# GPS_tracker_MCU.net
KiCad netlist of a schematic drawn in Altium Designer
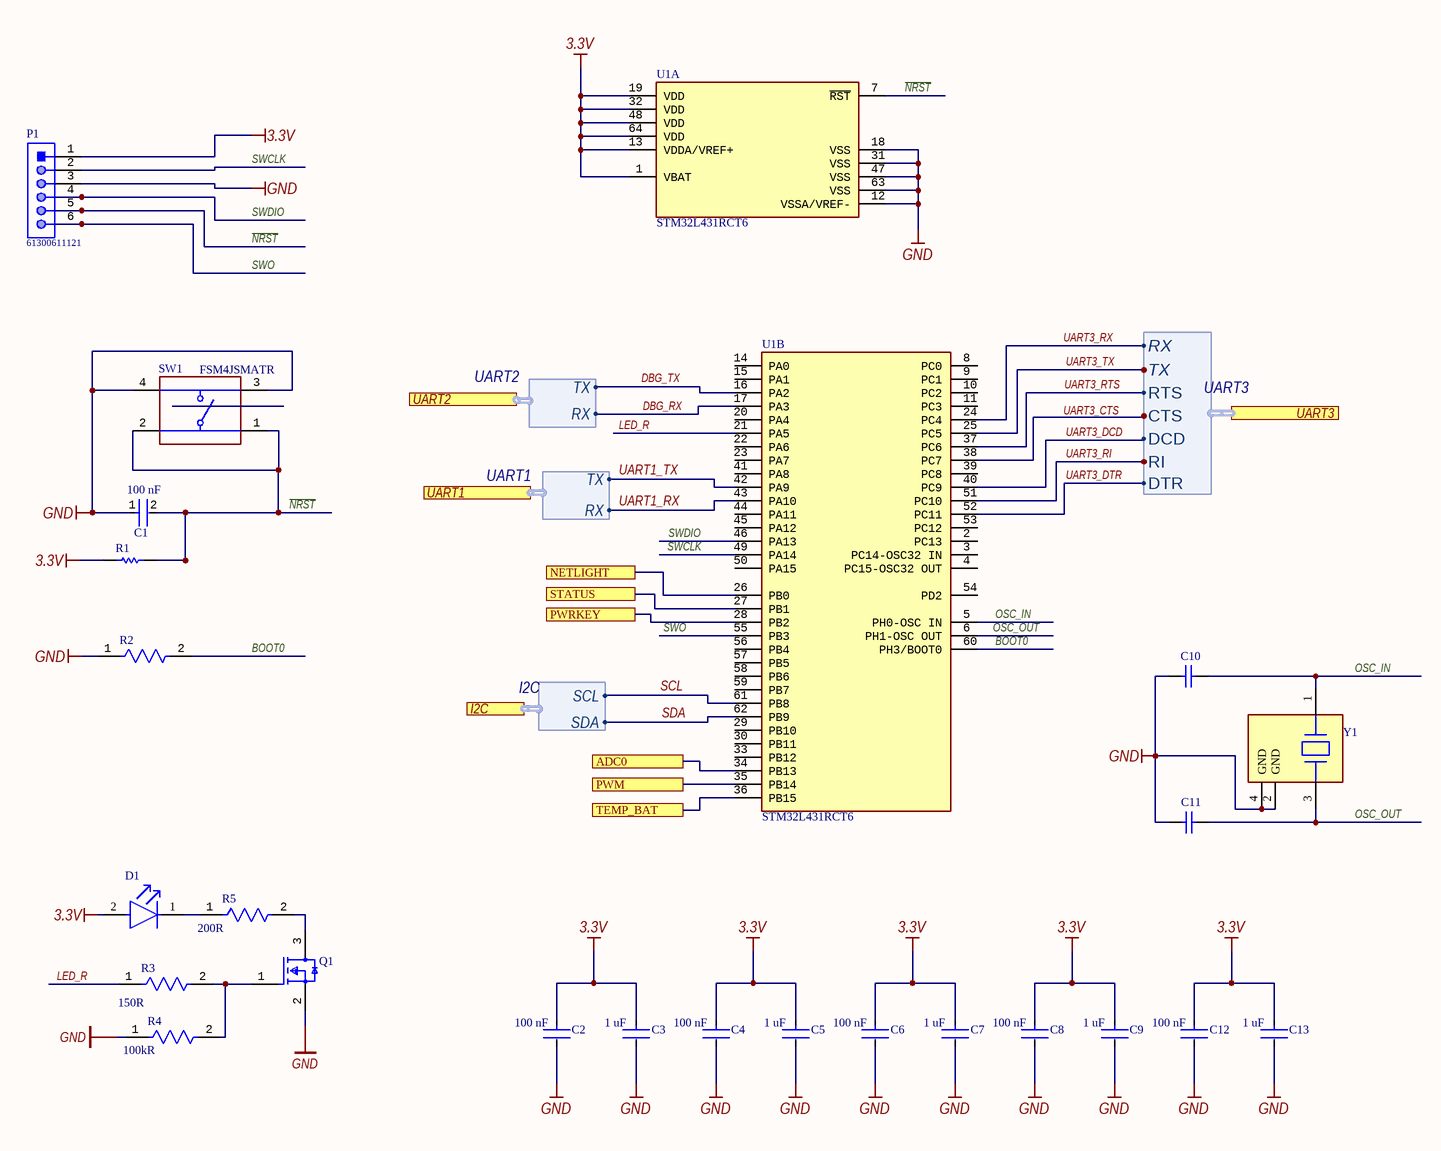
[diagram p0: GPS_tracker MCU.SchDoc]

(export (version "E")
  (design (tool "Eeschema 10.0.6"))
  (components
    (comp (ref "C1")
      (value "CC0603KRX7R7BB104")
      (footprint "FP-CC0603-DA-MFG")
      (description "CAP CER 0.1UF 16V X7R 0603")
      (fields
        (field (name "OCTOPART") "https://octopart.com/cc0603krx7r7bb104-yageo-192941")
        (field (name "TOLERANCE") "0.1")
        (field (name "CAPACITANCE") "100 nF")
      )
      (libsource (lib "") (part "11868f565c42a9108669ba33697ecf6_1"))
    )
    (comp (ref "C2")
      (value "CC0603KRX7R7BB104")
      (footprint "FP-CC0603-DA-MFG")
      (description "CAP CER 0.1UF 16V X7R 0603")
      (fields
        (field (name "OCTOPART") "https://octopart.com/cc0603krx7r7bb104-yageo-192941")
        (field (name "TOLERANCE") "0.1")
        (field (name "CAPACITANCE") "100 nF")
      )
      (libsource (lib "Altium Content Vault") (part "11868f565c42a9108669ba33697ecf6"))
    )
    (comp (ref "C3")
      (value "CC0603KRX7R7BB105")
      (footprint "FP-CC0603-DA-MFG")
      (description "CAP CER 1UF 16V X7R 0603")
      (fields
        (field (name "TOLERANCE") "0.1")
        (field (name "MANUFACTURER") "YAGEO")
        (field (name "CAPACITANCE") "1 uF")
      )
      (libsource (lib "Altium Content Vault") (part "11868f565c42a9108669ba33697ecf6"))
    )
    (comp (ref "C4")
      (value "CC0603KRX7R7BB104")
      (footprint "FP-CC0603-DA-MFG")
      (description "CAP CER 0.1UF 16V X7R 0603")
      (fields
        (field (name "OCTOPART") "https://octopart.com/cc0603krx7r7bb104-yageo-192941")
        (field (name "TOLERANCE") "0.1")
        (field (name "CAPACITANCE") "100 nF")
      )
      (libsource (lib "Altium Content Vault") (part "11868f565c42a9108669ba33697ecf6"))
    )
    (comp (ref "C5")
      (value "CC0603KRX7R7BB105")
      (footprint "FP-CC0603-DA-MFG")
      (description "CAP CER 1UF 16V X7R 0603")
      (fields
        (field (name "TOLERANCE") "0.1")
        (field (name "MANUFACTURER") "YAGEO")
        (field (name "CAPACITANCE") "1 uF")
      )
      (libsource (lib "Altium Content Vault") (part "11868f565c42a9108669ba33697ecf6"))
    )
    (comp (ref "C6")
      (value "CC0603KRX7R7BB104")
      (footprint "FP-CC0603-DA-MFG")
      (description "CAP CER 0.1UF 16V X7R 0603")
      (fields
        (field (name "OCTOPART") "https://octopart.com/cc0603krx7r7bb104-yageo-192941")
        (field (name "TOLERANCE") "0.1")
        (field (name "CAPACITANCE") "100 nF")
      )
      (libsource (lib "Altium Content Vault") (part "11868f565c42a9108669ba33697ecf6"))
    )
    (comp (ref "C7")
      (value "CC0603KRX7R7BB105")
      (footprint "FP-CC0603-DA-MFG")
      (description "CAP CER 1UF 16V X7R 0603")
      (fields
        (field (name "TOLERANCE") "0.1")
        (field (name "MANUFACTURER") "YAGEO")
        (field (name "CAPACITANCE") "1 uF")
      )
      (libsource (lib "Altium Content Vault") (part "11868f565c42a9108669ba33697ecf6"))
    )
    (comp (ref "C8")
      (value "CC0603KRX7R7BB104")
      (footprint "FP-CC0603-DA-MFG")
      (description "CAP CER 0.1UF 16V X7R 0603")
      (fields
        (field (name "OCTOPART") "https://octopart.com/cc0603krx7r7bb104-yageo-192941")
        (field (name "TOLERANCE") "0.1")
        (field (name "CAPACITANCE") "100 nF")
      )
      (libsource (lib "Altium Content Vault") (part "11868f565c42a9108669ba33697ecf6"))
    )
    (comp (ref "C9")
      (value "CC0603KRX7R7BB105")
      (footprint "FP-CC0603-DA-MFG")
      (description "CAP CER 1UF 16V X7R 0603")
      (fields
        (field (name "TOLERANCE") "0.1")
        (field (name "MANUFACTURER") "YAGEO")
        (field (name "CAPACITANCE") "1 uF")
      )
      (libsource (lib "Altium Content Vault") (part "11868f565c42a9108669ba33697ecf6"))
    )
    (comp (ref "C10")
      (value "CC0603JRNPO9BN180")
      (footprint "CAPC1608X90X40LL10T20")
      (description "Chip Capacitor, 18 pF, +/- 5%, 50 V, -55 to 125 degC, 0603 (1608 Metric), RoHS, Tape and Reel")
      (fields (field (name "TOLERANCE") "1%"))
      (libsource (lib "Altium Content Vault") (part "CAP-NP-2"))
    )
    (comp (ref "C11")
      (value "CC0603JRNPO9BN180")
      (footprint "CAPC1608X90X40LL10T20")
      (description "Chip Capacitor, 18 pF, +/- 5%, 50 V, -55 to 125 degC, 0603 (1608 Metric), RoHS, Tape and Reel")
      (fields (field (name "TOLERANCE") "1%"))
      (libsource (lib "Altium Content Vault") (part "CAP-NP-2"))
    )
    (comp (ref "C12")
      (value "CC0603KRX7R7BB104")
      (footprint "FP-CC0603-DA-MFG")
      (description "CAP CER 0.1UF 16V X7R 0603")
      (fields
        (field (name "OCTOPART") "https://octopart.com/cc0603krx7r7bb104-yageo-192941")
        (field (name "TOLERANCE") "0.1")
        (field (name "CAPACITANCE") "100 nF")
      )
      (libsource (lib "Altium Content Vault") (part "11868f565c42a9108669ba33697ecf6"))
    )
    (comp (ref "C13")
      (value "CC0603KRX7R7BB105")
      (footprint "FP-CC0603-DA-MFG")
      (description "CAP CER 1UF 16V X7R 0603")
      (fields
        (field (name "TOLERANCE") "0.1")
        (field (name "MANUFACTURER") "YAGEO")
        (field (name "CAPACITANCE") "1 uF")
      )
      (libsource (lib "Altium Content Vault") (part "11868f565c42a9108669ba33697ecf6"))
    )
    (comp (ref "D1")
      (value "150060RS75000")
      (footprint "FP-150060RS75000-MFG")
      (description "LED RED CLEAR 0603 SMD")
      (libsource (lib "Altium Content Vault") (part "8706943c75ba83719d021d2fdc84c58"))
    )
    (comp (ref "P1")
      (value "61300611121")
      (footprint "61300611121")
      (description "THT Vertical Pin Header WR-PHD, Pitch 2.54 mm, Single Row, 6 pins")
      (fields (field (name "MANUFACTURER") "Wurth Elektronik") (field (name "PUBLISHER") "WurthElektronik"))
      (libsource (lib "Altium Content Vault") (part "WE-CN-1P-M-R6"))
    )
    (comp (ref "Q1")
      (value "MMBF170LT1G")
      (footprint "FP-318-08-IPC_B")
      (description "MOSFET N-CH 60V 500MA SOT-23")
      (libsource (lib "Altium Content Vault") (part "0a9ea7c96deaaede766a5b531c28de0"))
    )
    (comp (ref "R1")
      (value "ERJ3EKF1002V")
      (footprint "RESC1609X55X30LL15T15")
      (description "Chip Resistor, 10 KOhm, +/- 1%, 0.1 W, -55 to 155 degC, 0603 (1608 Metric), RoHS, Tape and Reel")
      (fields (field (name "TOLERANCE") "1%") (field (name "MANUFACTURER") "Panasonic"))
      (libsource (lib "Altium Content Vault") (part "RES-2"))
    )
    (comp (ref "R2")
      (value "AC0603FR-071KL")
      (footprint "FP-AC0603-IPC_B")
      (description "RES 1kΩ 1.00% 0.1W 0603")
      (fields (field (name "TOLERANCE") "1%"))
      (libsource (lib "Altium Content Vault") (part "1029c3af85768c4190bb7ad29bc67b5"))
    )
    (comp (ref "R3")
      (value "AC0603FR-07150RL")
      (footprint "FP-AC0603-MFG")
      (description "RES 150Ω 1.00% 0.1W 0603")
      (fields (field (name "RESISTANCE") "150R") (field (name "TOLERANCE") "1%"))
      (libsource (lib "Altium Content Vault") (part "1029c3af85768c4190bb7ad29bc67b5"))
    )
    (comp (ref "R4")
      (value "RC0603FR-07100KL")
      (footprint "FP-RC0603-0_55-MFG")
      (description "RES SMD 100K OHM 1% 1/10W 0603")
      (fields (field (name "RESISTANCE") "100kR") (field (name "TOLERANCE") "1%"))
      (libsource (lib "Altium Content Vault") (part "1029c3af85768c4190bb7ad29bc67b5"))
    )
    (comp (ref "R5")
      (value "ERJ-3EKF2000V")
      (footprint "FP-ERJ3EK-IPC_C")
      (description "RES SMD 200 OHM 1% 1/10W 0603")
      (fields (field (name "TOLERANCE") "1%") (field (name "RESISTANCE") "200R"))
      (libsource (lib "Altium Content Vault") (part "1029c3af85768c4190bb7ad29bc67b5"))
    )
    (comp (ref "SW1")
      (value "FSM4JSMATR")
      (footprint "TECO-FSM4JSMATR_V")
      (description "Micro Miniature Push Button Switch FSM JSM, 50 mA, -35 to 85 degC, 4-Pin SMD, RoHS, Tape and Reel")
      (fields (field (name "MANUFACTURER") "TE Connectivity"))
      (libsource (lib "Components - 08.04.23 - 16.47") (part "CMP-2000-07486-1"))
    )
    (comp (ref "U1")
      (value "STM32L431RCT6")
      (footprint "FP-LQFP64-5W-MFG")
      (description "IC MCU 32BIT 256KB FLASH 64LQFP")
      (fields
        (field (name "MANUFACTURER") "STMicroelectronics")
        (field (name "OCTOPART") "https://octopart.com/stm32l431rct6-stmicroelectronics-74606534")
      )
      (libsource (lib "Altium Content Vault") (part "78361a36802d8896e128df32bdf1c40"))
    )
    (comp (ref "Y1")
      (value "ABM3B-8.000MHZ-B2-T")
      (footprint "FP-ABM3B-MFG")
      (description "Crystal 8MHz ±20ppm 18pF SMD-4 5mm x 3.2mm")
      (fields (field (name "TOLERANCE") "20ppm"))
      (libsource (lib "Altium Content Vault") (part "48e526d86b7f2615d98721063c72f49"))
    )
  )
  (nets
    (net (code "5") (name "/ADC0") (class "Default")
      (node (ref "U1") (pin "34") (pinfunction "PB13_34") (pintype "passive"))
    )
    (net (code "6") (name "/BOOT0") (class "Default")
      (node (ref "R2") (pin "2") (pinfunction "2_2") (pintype "passive"))
      (node (ref "U1") (pin "60") (pinfunction "PH3/BOOT0_60") (pintype "passive"))
    )
    (net (code "7") (name "/CTS") (class "Default")
      (node (ref "U1") (pin "38") (pinfunction "PC7_38") (pintype "passive"))
    )
    (net (code "10") (name "/LED_R") (class "Default")
      (node (ref "R3") (pin "1") (pinfunction "1_1") (pintype "passive"))
      (node (ref "U1") (pin "21") (pinfunction "PA5_21") (pintype "passive"))
    )
    (net (code "11") (name "/NETLIGHT") (class "Default")
      (node (ref "U1") (pin "26") (pinfunction "PB0_26") (pintype "passive"))
    )
    (net (code "12") (name "/OSC_IN") (class "Default")
      (node (ref "C10") (pin "2") (pinfunction "2_2") (pintype "passive"))
      (node (ref "U1") (pin "5") (pinfunction "PH0-OSC_IN_5") (pintype "passive"))
      (node (ref "Y1") (pin "1") (pinfunction "1_1") (pintype "passive"))
    )
    (net (code "13") (name "/OSC_OUT") (class "Default")
      (node (ref "C11") (pin "2") (pinfunction "2_2") (pintype "passive"))
      (node (ref "U1") (pin "6") (pinfunction "PH1-OSC_OUT_6") (pintype "passive"))
      (node (ref "Y1") (pin "3") (pinfunction "3_3") (pintype "passive"))
    )
    (net (code "14") (name "/PWM") (class "Default")
      (node (ref "U1") (pin "35") (pinfunction "PB14_35") (pintype "passive"))
    )
    (net (code "15") (name "/PWRKEY") (class "Default")
      (node (ref "U1") (pin "28") (pinfunction "PB2_28") (pintype "passive"))
    )
    (net (code "16") (name "/SCL") (class "Default")
      (node (ref "U1") (pin "61") (pinfunction "PB8_61") (pintype "passive"))
    )
    (net (code "17") (name "/SDA") (class "Default")
      (node (ref "U1") (pin "62") (pinfunction "PB9_62") (pintype "passive"))
    )
    (net (code "18") (name "/STATUS") (class "Default")
      (node (ref "U1") (pin "27") (pinfunction "PB1_27") (pintype "passive"))
    )
    (net (code "19") (name "/SWCLK") (class "Default")
      (node (ref "P1") (pin "2") (pinfunction "2_2") (pintype "passive"))
      (node (ref "U1") (pin "49") (pinfunction "PA14_49") (pintype "passive"))
    )
    (net (code "20") (name "/SWDIO") (class "Default")
      (node (ref "P1") (pin "4") (pinfunction "4_4") (pintype "passive"))
      (node (ref "U1") (pin "46") (pinfunction "PA13_46") (pintype "passive"))
    )
    (net (code "21") (name "/SWO") (class "Default")
      (node (ref "P1") (pin "6") (pinfunction "6_6") (pintype "passive"))
      (node (ref "U1") (pin "55") (pinfunction "PB3_55") (pintype "passive"))
    )
    (net (code "22") (name "/TEMP_BAT") (class "Default")
      (node (ref "U1") (pin "36") (pinfunction "PB15_36") (pintype "passive"))
    )
    (net (code "23") (name "/UART1_RX") (class "Default")
      (node (ref "U1") (pin "43") (pinfunction "PA10_43") (pintype "passive"))
    )
    (net (code "24") (name "/UART1_TX") (class "Default")
      (node (ref "U1") (pin "42") (pinfunction "PA9_42") (pintype "passive"))
    )
    (net (code "26") (name "/UART3_DCD") (class "Default")
      (node (ref "U1") (pin "40") (pinfunction "PC9_40") (pintype "passive"))
    )
    (net (code "27") (name "/UART3_DTR") (class "Default")
      (node (ref "U1") (pin "52") (pinfunction "PC11_52") (pintype "passive"))
    )
    (net (code "28") (name "/UART3_RI") (class "Default")
      (node (ref "U1") (pin "51") (pinfunction "PC10_51") (pintype "passive"))
    )
    (net (code "29") (name "/UART3_RTS") (class "Default")
      (node (ref "U1") (pin "37") (pinfunction "PC6_37") (pintype "passive"))
    )
    (net (code "31") (name "/UART3_TX") (class "Default")
      (node (ref "U1") (pin "25") (pinfunction "PC5_25") (pintype "passive"))
    )
    (net (code "36") (name "/~{NRST}") (class "Default")
      (node (ref "C1") (pin "2") (pinfunction "2_2") (pintype "passive"))
      (node (ref "P1") (pin "5") (pinfunction "5_5") (pintype "passive"))
      (node (ref "R1") (pin "2") (pinfunction "2_2") (pintype "passive"))
      (node (ref "SW1") (pin "1") (pinfunction "1_1") (pintype "passive"))
      (node (ref "SW1") (pin "2") (pinfunction "2_2") (pintype "passive"))
      (node (ref "U1") (pin "7") (pinfunction "~{RST}_7") (pintype "passive"))
    )
    (net (code "37") (name "3.3V") (class "Default")
      (node (ref "C12") (pin "1") (pinfunction "1_1") (pintype "passive"))
      (node (ref "C13") (pin "1") (pinfunction "1_1") (pintype "passive"))
      (node (ref "C2") (pin "1") (pinfunction "1_1") (pintype "passive"))
      (node (ref "C3") (pin "1") (pinfunction "1_1") (pintype "passive"))
      (node (ref "C4") (pin "1") (pinfunction "1_1") (pintype "passive"))
      (node (ref "C5") (pin "1") (pinfunction "1_1") (pintype "passive"))
      (node (ref "C6") (pin "1") (pinfunction "1_1") (pintype "passive"))
      (node (ref "C7") (pin "1") (pinfunction "1_1") (pintype "passive"))
      (node (ref "C8") (pin "1") (pinfunction "1_1") (pintype "passive"))
      (node (ref "C9") (pin "1") (pinfunction "1_1") (pintype "passive"))
      (node (ref "D1") (pin "2") (pinfunction "A_2") (pintype "passive"))
      (node (ref "P1") (pin "1") (pinfunction "1_1") (pintype "passive"))
      (node (ref "R1") (pin "1") (pinfunction "1_1") (pintype "passive"))
      (node (ref "U1") (pin "1") (pinfunction "VBAT_1") (pintype "passive"))
      (node (ref "U1") (pin "13") (pinfunction "VDDA/VREF+_13") (pintype "passive"))
      (node (ref "U1") (pin "19") (pinfunction "VDD_19") (pintype "passive"))
      (node (ref "U1") (pin "32") (pinfunction "VDD_32") (pintype "passive"))
      (node (ref "U1") (pin "48") (pinfunction "VDD_48") (pintype "passive"))
      (node (ref "U1") (pin "64") (pinfunction "VDD_64") (pintype "passive"))
    )
    (net (code "38") (name "GND") (class "Default")
      (node (ref "C1") (pin "1") (pinfunction "1_1") (pintype "passive"))
      (node (ref "C10") (pin "1") (pinfunction "1_1") (pintype "passive"))
      (node (ref "C11") (pin "1") (pinfunction "1_1") (pintype "passive"))
      (node (ref "C12") (pin "2") (pinfunction "2_2") (pintype "passive"))
      (node (ref "C13") (pin "2") (pinfunction "2_2") (pintype "passive"))
      (node (ref "C2") (pin "2") (pinfunction "2_2") (pintype "passive"))
      (node (ref "C3") (pin "2") (pinfunction "2_2") (pintype "passive"))
      (node (ref "C4") (pin "2") (pinfunction "2_2") (pintype "passive"))
      (node (ref "C5") (pin "2") (pinfunction "2_2") (pintype "passive"))
      (node (ref "C6") (pin "2") (pinfunction "2_2") (pintype "passive"))
      (node (ref "C7") (pin "2") (pinfunction "2_2") (pintype "passive"))
      (node (ref "C8") (pin "2") (pinfunction "2_2") (pintype "passive"))
      (node (ref "C9") (pin "2") (pinfunction "2_2") (pintype "passive"))
      (node (ref "P1") (pin "3") (pinfunction "3_3") (pintype "passive"))
      (node (ref "Q1") (pin "2") (pinfunction "S_2") (pintype "passive"))
      (node (ref "R2") (pin "1") (pinfunction "1_1") (pintype "passive"))
      (node (ref "R4") (pin "1") (pinfunction "1_1") (pintype "passive"))
      (node (ref "SW1") (pin "3") (pinfunction "3_3") (pintype "passive"))
      (node (ref "SW1") (pin "4") (pinfunction "4_4") (pintype "passive"))
      (node (ref "U1") (pin "12") (pinfunction "VSSA/VREF-_12") (pintype "passive"))
      (node (ref "U1") (pin "18") (pinfunction "VSS_18") (pintype "passive"))
      (node (ref "U1") (pin "31") (pinfunction "VSS_31") (pintype "passive"))
      (node (ref "U1") (pin "47") (pinfunction "VSS_47") (pintype "passive"))
      (node (ref "U1") (pin "63") (pinfunction "VSS_63") (pintype "passive"))
      (node (ref "Y1") (pin "2") (pinfunction "GND_2") (pintype "power_in"))
      (node (ref "Y1") (pin "4") (pinfunction "GND_4") (pintype "power_in"))
    )
    (net (code "39") (name "Net-(D1-C)") (class "Default")
      (node (ref "D1") (pin "1") (pinfunction "C_1") (pintype "passive"))
      (node (ref "R5") (pin "1") (pinfunction "1_1") (pintype "passive"))
    )
    (net (code "40") (name "Net-(Q1-D)") (class "Default")
      (node (ref "Q1") (pin "3") (pinfunction "D_3") (pintype "passive"))
      (node (ref "R5") (pin "2") (pinfunction "2_2") (pintype "passive"))
    )
    (net (code "41") (name "Net-(Q1-G)") (class "Default")
      (node (ref "Q1") (pin "1") (pinfunction "G_1") (pintype "passive"))
      (node (ref "R3") (pin "2") (pinfunction "2_2") (pintype "passive"))
      (node (ref "R4") (pin "2") (pinfunction "2_2") (pintype "passive"))
    )
    (net (code "42") (name "unconnected-(U1B-PA0-Pad14)") (class "Default")
      (node (ref "U1") (pin "14") (pinfunction "PA0_14") (pintype "passive"))
    )
    (net (code "43") (name "unconnected-(U1B-PA1-Pad15)") (class "Default")
      (node (ref "U1") (pin "15") (pinfunction "PA1_15") (pintype "passive"))
    )
    (net (code "44") (name "unconnected-(U1B-PA2-Pad16)") (class "Default")
      (node (ref "U1") (pin "16") (pinfunction "PA2_16") (pintype "passive"))
    )
    (net (code "45") (name "unconnected-(U1B-PA3-Pad17)") (class "Default")
      (node (ref "U1") (pin "17") (pinfunction "PA3_17") (pintype "passive"))
    )
    (net (code "46") (name "unconnected-(U1B-PA4-Pad20)") (class "Default")
      (node (ref "U1") (pin "20") (pinfunction "PA4_20") (pintype "passive"))
    )
    (net (code "47") (name "unconnected-(U1B-PA6-Pad22)") (class "Default")
      (node (ref "U1") (pin "22") (pinfunction "PA6_22") (pintype "passive"))
    )
    (net (code "48") (name "unconnected-(U1B-PA7-Pad23)") (class "Default")
      (node (ref "U1") (pin "23") (pinfunction "PA7_23") (pintype "passive"))
    )
    (net (code "49") (name "unconnected-(U1B-PA8-Pad41)") (class "Default")
      (node (ref "U1") (pin "41") (pinfunction "PA8_41") (pintype "passive"))
    )
    (net (code "50") (name "unconnected-(U1B-PA11-Pad44)") (class "Default")
      (node (ref "U1") (pin "44") (pinfunction "PA11_44") (pintype "passive"))
    )
    (net (code "51") (name "unconnected-(U1B-PA12-Pad45)") (class "Default")
      (node (ref "U1") (pin "45") (pinfunction "PA12_45") (pintype "passive"))
    )
    (net (code "52") (name "unconnected-(U1B-PA15-Pad50)") (class "Default")
      (node (ref "U1") (pin "50") (pinfunction "PA15_50") (pintype "passive"))
    )
    (net (code "53") (name "unconnected-(U1B-PB4-Pad56)") (class "Default")
      (node (ref "U1") (pin "56") (pinfunction "PB4_56") (pintype "passive"))
    )
    (net (code "54") (name "unconnected-(U1B-PB5-Pad57)") (class "Default")
      (node (ref "U1") (pin "57") (pinfunction "PB5_57") (pintype "passive"))
    )
    (net (code "55") (name "unconnected-(U1B-PB6-Pad58)") (class "Default")
      (node (ref "U1") (pin "58") (pinfunction "PB6_58") (pintype "passive"))
    )
    (net (code "56") (name "unconnected-(U1B-PB7-Pad59)") (class "Default")
      (node (ref "U1") (pin "59") (pinfunction "PB7_59") (pintype "passive"))
    )
    (net (code "57") (name "unconnected-(U1B-PB10-Pad29)") (class "Default")
      (node (ref "U1") (pin "29") (pinfunction "PB10_29") (pintype "passive"))
    )
    (net (code "58") (name "unconnected-(U1B-PB11-Pad30)") (class "Default")
      (node (ref "U1") (pin "30") (pinfunction "PB11_30") (pintype "passive"))
    )
    (net (code "59") (name "unconnected-(U1B-PB12-Pad33)") (class "Default")
      (node (ref "U1") (pin "33") (pinfunction "PB12_33") (pintype "passive"))
    )
    (net (code "60") (name "unconnected-(U1B-PC0-Pad8)") (class "Default")
      (node (ref "U1") (pin "8") (pinfunction "PC0_8") (pintype "passive"))
    )
    (net (code "61") (name "unconnected-(U1B-PC1-Pad9)") (class "Default")
      (node (ref "U1") (pin "9") (pinfunction "PC1_9") (pintype "passive"))
    )
    (net (code "62") (name "unconnected-(U1B-PC2-Pad10)") (class "Default")
      (node (ref "U1") (pin "10") (pinfunction "PC2_10") (pintype "passive"))
    )
    (net (code "63") (name "unconnected-(U1B-PC3-Pad11)") (class "Default")
      (node (ref "U1") (pin "11") (pinfunction "PC3_11") (pintype "passive"))
    )
    (net (code "64") (name "unconnected-(U1B-PC4-Pad24)") (class "Default")
      (node (ref "U1") (pin "24") (pinfunction "PC4_24") (pintype "passive"))
    )
    (net (code "65") (name "unconnected-(U1B-PC8-Pad39)") (class "Default")
      (node (ref "U1") (pin "39") (pinfunction "PC8_39") (pintype "passive"))
    )
    (net (code "66") (name "unconnected-(U1B-PC12-Pad53)") (class "Default")
      (node (ref "U1") (pin "53") (pinfunction "PC12_53") (pintype "passive"))
    )
    (net (code "67") (name "unconnected-(U1B-PC13-Pad2)") (class "Default")
      (node (ref "U1") (pin "2") (pinfunction "PC13_2") (pintype "passive"))
    )
    (net (code "68") (name "unconnected-(U1B-PC14-OSC32_IN-Pad3)") (class "Default")
      (node (ref "U1") (pin "3") (pinfunction "PC14-OSC32_IN_3") (pintype "passive"))
    )
    (net (code "69") (name "unconnected-(U1B-PC15-OSC32_OUT-Pad4)") (class "Default")
      (node (ref "U1") (pin "4") (pinfunction "PC15-OSC32_OUT_4") (pintype "passive"))
    )
    (net (code "70") (name "unconnected-(U1B-PD2-Pad54)") (class "Default")
      (node (ref "U1") (pin "54") (pinfunction "PD2_54") (pintype "passive"))
    )
  )
)
